# design.net
KiCad netlist of a schematic drawn in Altium Designer
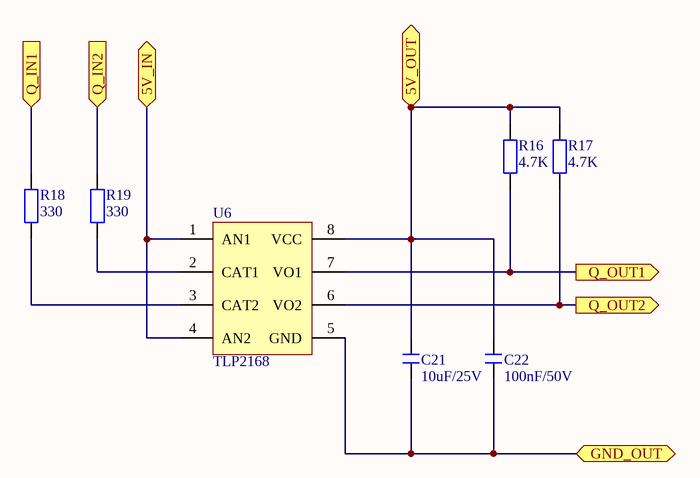
[diagram p0: 第二路数字隔离原理图.SchDoc]

(export (version "E")
  (design (tool "Eeschema 10.0.6"))
  (components
    (comp (ref "C21")
      (value "10uF/25V")
      (footprint "C 0603_M")
      (description "无极性贴片电容")
      (fields (field (name "版权归属") "源创客"))
      (libsource (lib "3.1   - 电阻-电容-电感") (part "C"))
    )
    (comp (ref "C22")
      (value "100nF/50V")
      (footprint "C 0603_M")
      (description "无极性贴片电容")
      (fields (field (name "版权归属") "源创客"))
      (libsource (lib "3.1   - 电阻-电容-电感") (part "C"))
    )
    (comp (ref "R16")
      (value "4.7K")
      (footprint "R 0603_M")
      (description "贴片电阻")
      (fields (field (name "版权归属") "源创客"))
      (libsource (lib "3.1   - 电阻-电容-电感") (part "R"))
    )
    (comp (ref "R17")
      (value "4.7K")
      (footprint "R 0603_M")
      (description "贴片电阻")
      (fields (field (name "版权归属") "源创客"))
      (libsource (lib "3.1   - 电阻-电容-电感") (part "R"))
    )
    (comp (ref "R18")
      (value "330")
      (footprint "R 0603_M")
      (description "贴片电阻")
      (fields (field (name "版权归属") "源创客"))
      (libsource (lib "3.1   - 电阻-电容-电感") (part "R"))
    )
    (comp (ref "R19")
      (value "330")
      (footprint "R 0603_M")
      (description "贴片电阻")
      (fields (field (name "版权归属") "源创客"))
      (libsource (lib "3.1   - 电阻-电容-电感") (part "R"))
    )
    (comp (ref "U6")
      (value "TLP2168")
      (footprint "SOP8_N")
      (description "高速双通道隔离光耦")
      (libsource (lib "1.1   - IC芯片") (part "TLP2168"))
    )
  )
  (nets
    (net (code "1") (name "/5V_IN") (class "Default")
      (node (ref "U6") (pin "1") (pinfunction "AN1_1") (pintype "passive"))
      (node (ref "U6") (pin "4") (pinfunction "AN2_4") (pintype "passive"))
    )
    (net (code "2") (name "/5V_OUT") (class "Default")
      (node (ref "C21") (pin "1") (pinfunction "1_1") (pintype "passive"))
      (node (ref "C22") (pin "2") (pinfunction "2_2") (pintype "passive"))
      (node (ref "R16") (pin "2") (pinfunction "2_2") (pintype "passive"))
      (node (ref "R17") (pin "2") (pinfunction "2_2") (pintype "passive"))
      (node (ref "U6") (pin "8") (pinfunction "VCC_8") (pintype "passive"))
    )
    (net (code "3") (name "/GND_OUT") (class "Default")
      (node (ref "C21") (pin "2") (pinfunction "2_2") (pintype "passive"))
      (node (ref "C22") (pin "1") (pinfunction "1_1") (pintype "passive"))
      (node (ref "U6") (pin "5") (pinfunction "GND_5") (pintype "passive"))
    )
    (net (code "4") (name "/Q_IN1") (class "Default")
      (node (ref "R18") (pin "2") (pinfunction "2_2") (pintype "passive"))
    )
    (net (code "5") (name "/Q_IN2") (class "Default")
      (node (ref "R19") (pin "2") (pinfunction "2_2") (pintype "passive"))
    )
    (net (code "6") (name "/Q_OUT1") (class "Default")
      (node (ref "R16") (pin "1") (pinfunction "1_1") (pintype "passive"))
      (node (ref "U6") (pin "7") (pinfunction "VO1_7") (pintype "passive"))
    )
    (net (code "7") (name "/Q_OUT2") (class "Default")
      (node (ref "R17") (pin "1") (pinfunction "1_1") (pintype "passive"))
      (node (ref "U6") (pin "6") (pinfunction "VO2_6") (pintype "passive"))
    )
    (net (code "8") (name "Net-(U6-CAT1)") (class "Default")
      (node (ref "R19") (pin "1") (pinfunction "1_1") (pintype "passive"))
      (node (ref "U6") (pin "2") (pinfunction "CAT1_2") (pintype "passive"))
    )
    (net (code "9") (name "Net-(U6-CAT2)") (class "Default")
      (node (ref "R18") (pin "1") (pinfunction "1_1") (pintype "passive"))
      (node (ref "U6") (pin "3") (pinfunction "CAT2_3") (pintype "passive"))
    )
  )
)
